# motorctrl.net
KiCad netlist of a schematic drawn in EAGLE
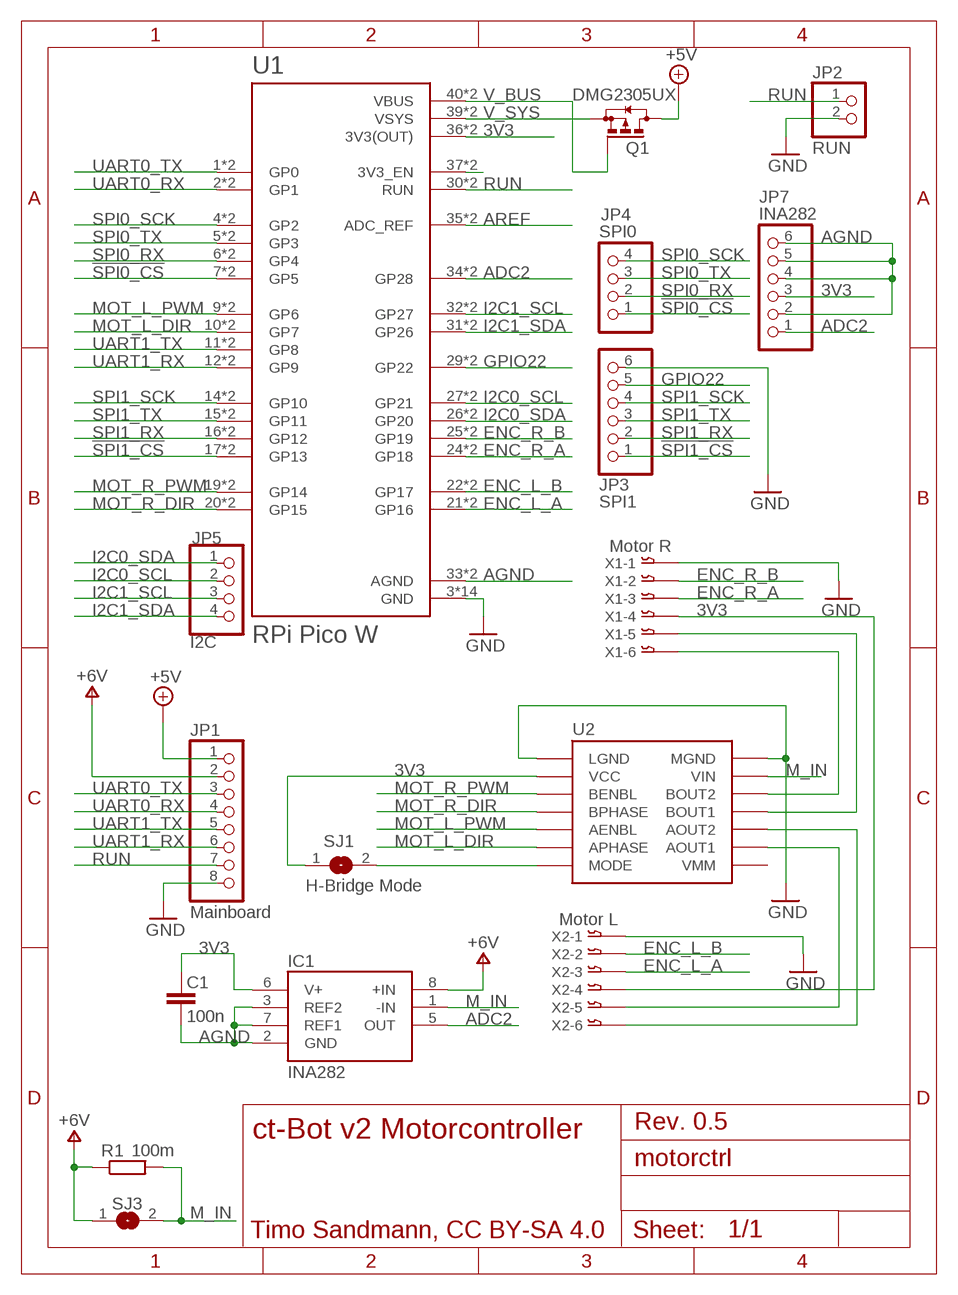
[diagram p0: schematic, sheet 1]

(export (version "E")
  (design (tool "Eeschema 10.0.6"))
  (components
    (comp (ref "C1")
      (value "100n")
      (footprint "eagle-import:C0805")
      (libsource (lib "eagle-import") (part "C-EUC0805"))
    )
    (comp (ref "IC1")
      (value "INA282")
      (footprint "eagle-import:SO08")
      (fields (field (name "MF") "TEXAS INSTRUMENTS"))
      (libsource (lib "eagle-import") (part "INA28AID"))
    )
    (comp (ref "JP1")
      (value "Mainboard")
      (footprint "eagle-import:1X08")
      (libsource (lib "eagle-import") (part "PINHD-1X8"))
    )
    (comp (ref "JP2")
      (value "RUN")
      (footprint "eagle-import:1X02")
      (libsource (lib "eagle-import") (part "PINHD-1X2"))
    )
    (comp (ref "JP3")
      (value "SPI1")
      (footprint "eagle-import:1X06")
      (libsource (lib "eagle-import") (part "PINHD-1X6"))
    )
    (comp (ref "JP4")
      (value "SPI0")
      (footprint "eagle-import:1X04")
      (libsource (lib "eagle-import") (part "PINHD-1X4"))
    )
    (comp (ref "JP5")
      (value "I2C")
      (footprint "eagle-import:1X04")
      (libsource (lib "eagle-import") (part "PINHD-1X4"))
    )
    (comp (ref "JP7")
      (value "INA282")
      (footprint "eagle-import:1X06")
      (libsource (lib "eagle-import") (part "PINHD-1X6"))
    )
    (comp (ref "Q1")
      (value "DMG2305UX")
      (footprint "eagle-import:SOT23")
      (libsource (lib "eagle-import") (part "BSS84"))
    )
    (comp (ref "R1")
      (value "100m")
      (footprint "eagle-import:R2512")
      (libsource (lib "eagle-import") (part "R-EU_R2512"))
    )
    (comp (ref "SJ1")
      (value "H-Bridge Mode")
      (footprint "eagle-import:SJ")
      (libsource (lib "eagle-import") (part "SJ"))
    )
    (comp (ref "SJ3")
      (value "VREF")
      (footprint "eagle-import:SJ")
      (libsource (lib "eagle-import") (part "SJ"))
    )
    (comp (ref "U1")
      (value "RPi Pico W")
      (footprint "eagle-import:PICO-PKG-NO_DEBUG")
      (libsource (lib "eagle-import") (part "RASPBERRY_PICO-NO_DEBUG"))
    )
    (comp (ref "U2")
      (value "DRV8835THROUGHHOLE")
      (footprint "eagle-import:DRV8835")
      (libsource (lib "eagle-import") (part "DRV8835THROUGHHOLE"))
    )
    (comp (ref "X1")
      (value "Motor R")
      (footprint "eagle-import:B6B-XH")
      (libsource (lib "eagle-import") (part "06-JST-B6B-XH-A"))
    )
    (comp (ref "X2")
      (value "Motor L")
      (footprint "eagle-import:B6B-XH")
      (libsource (lib "eagle-import") (part "06-JST-B6B-XH-A"))
    )
  )
  (nets
    (net (code "1") (name "+5V") (class "Default")
      (node (ref "JP1") (pin "1") (pinfunction "1_1") (pintype "passive"))
      (node (ref "Q1") (pin "3") (pinfunction "D_3") (pintype "passive"))
    )
    (net (code "2") (name "+6V") (class "Default")
      (node (ref "IC1") (pin "8") (pinfunction "+IN_8") (pintype "input"))
      (node (ref "JP1") (pin "2") (pinfunction "2_2") (pintype "passive"))
      (node (ref "R1") (pin "1") (pinfunction "1_1") (pintype "passive"))
      (node (ref "SJ3") (pin "1") (pinfunction "1_1") (pintype "passive"))
    )
    (net (code "3") (name "/3V3") (class "Default")
      (node (ref "C1") (pin "2") (pinfunction "2_2") (pintype "passive"))
      (node (ref "IC1") (pin "6") (pinfunction "V+_6") (pintype "power_in"))
      (node (ref "JP7") (pin "3") (pinfunction "3_3") (pintype "passive"))
      (node (ref "SJ1") (pin "1") (pinfunction "1_1") (pintype "passive"))
      (node (ref "U1") (pin "36") (pinfunction "3V3(OUT)_36") (pintype "power_in"))
      (node (ref "U1") (pin "P$36") (pinfunction "3V3(OUT)_P$36") (pintype "power_in"))
      (node (ref "U2") (pin "VCC") (pinfunction "VCC_VCC") (pintype "bidirectional"))
      (node (ref "X1") (pin "P$4") (pinfunction "1_P$4") (pintype "passive"))
      (node (ref "X2") (pin "P$4") (pinfunction "1_P$4") (pintype "passive"))
    )
    (net (code "4") (name "/ADC2") (class "Default")
      (node (ref "IC1") (pin "5") (pinfunction "OUT_5") (pintype "output"))
      (node (ref "JP7") (pin "1") (pinfunction "1_1") (pintype "passive"))
      (node (ref "U1") (pin "34") (pinfunction "GP28_34") (pintype "bidirectional"))
      (node (ref "U1") (pin "P$34") (pinfunction "GP28_P$34") (pintype "bidirectional"))
    )
    (net (code "5") (name "/AGND") (class "Default")
      (node (ref "C1") (pin "1") (pinfunction "1_1") (pintype "passive"))
      (node (ref "IC1") (pin "2") (pinfunction "GND_2") (pintype "power_in"))
      (node (ref "IC1") (pin "3") (pinfunction "REF2_3") (pintype "input"))
      (node (ref "IC1") (pin "7") (pinfunction "REF1_7") (pintype "input"))
      (node (ref "JP7") (pin "2") (pinfunction "2_2") (pintype "passive"))
      (node (ref "JP7") (pin "4") (pinfunction "4_4") (pintype "passive"))
      (node (ref "JP7") (pin "5") (pinfunction "5_5") (pintype "passive"))
      (node (ref "JP7") (pin "6") (pinfunction "6_6") (pintype "passive"))
      (node (ref "U1") (pin "33") (pinfunction "AGND_33") (pintype "input"))
      (node (ref "U1") (pin "P$33") (pinfunction "AGND_P$33") (pintype "input"))
    )
    (net (code "6") (name "/AREF") (class "Default")
      (node (ref "U1") (pin "35") (pinfunction "ADC_REF_35") (pintype "input"))
      (node (ref "U1") (pin "P$35") (pinfunction "ADC_REF_P$35") (pintype "input"))
    )
    (net (code "7") (name "/ENC_L_A") (class "Default")
      (node (ref "U1") (pin "21") (pinfunction "GP16_21") (pintype "bidirectional"))
      (node (ref "U1") (pin "P$21") (pinfunction "GP16_P$21") (pintype "bidirectional"))
      (node (ref "X2") (pin "P$3") (pinfunction "1_P$3") (pintype "passive"))
    )
    (net (code "8") (name "/ENC_L_B") (class "Default")
      (node (ref "U1") (pin "22") (pinfunction "GP17_22") (pintype "bidirectional"))
      (node (ref "U1") (pin "P$22") (pinfunction "GP17_P$22") (pintype "bidirectional"))
      (node (ref "X2") (pin "P$2") (pinfunction "1_P$2") (pintype "passive"))
    )
    (net (code "9") (name "/ENC_R_A") (class "Default")
      (node (ref "U1") (pin "24") (pinfunction "GP18_24") (pintype "bidirectional"))
      (node (ref "U1") (pin "P$24") (pinfunction "GP18_P$24") (pintype "bidirectional"))
      (node (ref "X1") (pin "P$3") (pinfunction "1_P$3") (pintype "passive"))
    )
    (net (code "10") (name "/ENC_R_B") (class "Default")
      (node (ref "U1") (pin "25") (pinfunction "GP19_25") (pintype "bidirectional"))
      (node (ref "U1") (pin "P$25") (pinfunction "GP19_P$25") (pintype "bidirectional"))
      (node (ref "X1") (pin "P$2") (pinfunction "1_P$2") (pintype "passive"))
    )
    (net (code "11") (name "/GPIO22") (class "Default")
      (node (ref "JP3") (pin "5") (pinfunction "5_5") (pintype "passive"))
      (node (ref "U1") (pin "29") (pinfunction "GP22_29") (pintype "bidirectional"))
      (node (ref "U1") (pin "P$29") (pinfunction "GP22_P$29") (pintype "bidirectional"))
    )
    (net (code "12") (name "/I2C0_SCL") (class "Default")
      (node (ref "JP5") (pin "2") (pinfunction "2_2") (pintype "passive"))
      (node (ref "U1") (pin "27") (pinfunction "GP21_27") (pintype "bidirectional"))
      (node (ref "U1") (pin "P$27") (pinfunction "GP21_P$27") (pintype "bidirectional"))
    )
    (net (code "13") (name "/I2C0_SDA") (class "Default")
      (node (ref "JP5") (pin "1") (pinfunction "1_1") (pintype "passive"))
      (node (ref "U1") (pin "26") (pinfunction "GP20_26") (pintype "bidirectional"))
      (node (ref "U1") (pin "P$26") (pinfunction "GP20_P$26") (pintype "bidirectional"))
    )
    (net (code "14") (name "/I2C1_SCL") (class "Default")
      (node (ref "JP5") (pin "3") (pinfunction "3_3") (pintype "passive"))
      (node (ref "U1") (pin "32") (pinfunction "GP27_32") (pintype "bidirectional"))
      (node (ref "U1") (pin "P$32") (pinfunction "GP27_P$32") (pintype "bidirectional"))
    )
    (net (code "15") (name "/I2C1_SDA") (class "Default")
      (node (ref "JP5") (pin "4") (pinfunction "4_4") (pintype "passive"))
      (node (ref "U1") (pin "31") (pinfunction "GP26_31") (pintype "bidirectional"))
      (node (ref "U1") (pin "P$31") (pinfunction "GP26_P$31") (pintype "bidirectional"))
    )
    (net (code "16") (name "/MOT_L_DIR") (class "Default")
      (node (ref "U1") (pin "10") (pinfunction "GP7_10") (pintype "bidirectional"))
      (node (ref "U1") (pin "P$10") (pinfunction "GP7_P$10") (pintype "bidirectional"))
      (node (ref "U2") (pin "APHASE") (pinfunction "APHASE_APHASE") (pintype "bidirectional"))
    )
    (net (code "17") (name "/MOT_L_PWM") (class "Default")
      (node (ref "U1") (pin "9") (pinfunction "GP6_9") (pintype "bidirectional"))
      (node (ref "U1") (pin "P$9") (pinfunction "GP6_P$9") (pintype "bidirectional"))
      (node (ref "U2") (pin "AENBL") (pinfunction "AENBL_AENBL") (pintype "bidirectional"))
    )
    (net (code "18") (name "/MOT_R_DIR") (class "Default")
      (node (ref "U1") (pin "20") (pinfunction "GP15_20") (pintype "bidirectional"))
      (node (ref "U1") (pin "P$20") (pinfunction "GP15_P$20") (pintype "bidirectional"))
      (node (ref "U2") (pin "BPHASE") (pinfunction "BPHASE_BPHASE") (pintype "bidirectional"))
    )
    (net (code "19") (name "/MOT_R_PWM") (class "Default")
      (node (ref "U1") (pin "19") (pinfunction "GP14_19") (pintype "bidirectional"))
      (node (ref "U1") (pin "P$19") (pinfunction "GP14_P$19") (pintype "bidirectional"))
      (node (ref "U2") (pin "BENBL") (pinfunction "BENBL_BENBL") (pintype "bidirectional"))
    )
    (net (code "20") (name "/M_IN") (class "Default")
      (node (ref "IC1") (pin "1") (pinfunction "-IN_1") (pintype "input"))
      (node (ref "R1") (pin "2") (pinfunction "2_2") (pintype "passive"))
      (node (ref "SJ3") (pin "2") (pinfunction "2_2") (pintype "passive"))
      (node (ref "U2") (pin "VIN") (pinfunction "VIN_VIN") (pintype "bidirectional"))
    )
    (net (code "21") (name "/RUN") (class "Default")
      (node (ref "JP1") (pin "7") (pinfunction "7_7") (pintype "passive"))
      (node (ref "JP2") (pin "1") (pinfunction "1_1") (pintype "passive"))
      (node (ref "U1") (pin "30") (pinfunction "RUN_30") (pintype "input"))
      (node (ref "U1") (pin "P$30") (pinfunction "RUN_P$30") (pintype "input"))
    )
    (net (code "22") (name "/SPI0_RX") (class "Default")
      (node (ref "JP4") (pin "2") (pinfunction "2_2") (pintype "passive"))
      (node (ref "U1") (pin "6") (pinfunction "GP4_6") (pintype "bidirectional"))
      (node (ref "U1") (pin "P$6") (pinfunction "GP4_P$6") (pintype "bidirectional"))
    )
    (net (code "23") (name "/SPI0_SCK") (class "Default")
      (node (ref "JP4") (pin "4") (pinfunction "4_4") (pintype "passive"))
      (node (ref "U1") (pin "4") (pinfunction "GP2_4") (pintype "bidirectional"))
      (node (ref "U1") (pin "P$4") (pinfunction "GP2_P$4") (pintype "bidirectional"))
    )
    (net (code "24") (name "/SPI0_TX") (class "Default")
      (node (ref "JP4") (pin "3") (pinfunction "3_3") (pintype "passive"))
      (node (ref "U1") (pin "5") (pinfunction "GP3_5") (pintype "bidirectional"))
      (node (ref "U1") (pin "P$5") (pinfunction "GP3_P$5") (pintype "bidirectional"))
    )
    (net (code "25") (name "/SPI1_RX") (class "Default")
      (node (ref "JP3") (pin "2") (pinfunction "2_2") (pintype "passive"))
      (node (ref "U1") (pin "16") (pinfunction "GP12_16") (pintype "bidirectional"))
      (node (ref "U1") (pin "P$16") (pinfunction "GP12_P$16") (pintype "bidirectional"))
    )
    (net (code "26") (name "/SPI1_SCK") (class "Default")
      (node (ref "JP3") (pin "4") (pinfunction "4_4") (pintype "passive"))
      (node (ref "U1") (pin "14") (pinfunction "GP10_14") (pintype "bidirectional"))
      (node (ref "U1") (pin "P$14") (pinfunction "GP10_P$14") (pintype "bidirectional"))
    )
    (net (code "27") (name "/SPI1_TX") (class "Default")
      (node (ref "JP3") (pin "3") (pinfunction "3_3") (pintype "passive"))
      (node (ref "U1") (pin "15") (pinfunction "GP11_15") (pintype "bidirectional"))
      (node (ref "U1") (pin "P$15") (pinfunction "GP11_P$15") (pintype "bidirectional"))
    )
    (net (code "28") (name "/UART0_RX") (class "Default")
      (node (ref "JP1") (pin "4") (pinfunction "4_4") (pintype "passive"))
      (node (ref "U1") (pin "2") (pinfunction "GP1_2") (pintype "bidirectional"))
      (node (ref "U1") (pin "P$2") (pinfunction "GP1_P$2") (pintype "bidirectional"))
    )
    (net (code "29") (name "/UART0_TX") (class "Default")
      (node (ref "JP1") (pin "3") (pinfunction "3_3") (pintype "passive"))
      (node (ref "U1") (pin "1") (pinfunction "GP0_1") (pintype "bidirectional"))
      (node (ref "U1") (pin "P$1") (pinfunction "GP0_P$1") (pintype "bidirectional"))
    )
    (net (code "30") (name "/UART1_RX") (class "Default")
      (node (ref "JP1") (pin "6") (pinfunction "6_6") (pintype "passive"))
      (node (ref "U1") (pin "12") (pinfunction "GP9_12") (pintype "bidirectional"))
      (node (ref "U1") (pin "P$12") (pinfunction "GP9_P$12") (pintype "bidirectional"))
    )
    (net (code "31") (name "/UART1_TX") (class "Default")
      (node (ref "JP1") (pin "5") (pinfunction "5_5") (pintype "passive"))
      (node (ref "U1") (pin "11") (pinfunction "GP8_11") (pintype "bidirectional"))
      (node (ref "U1") (pin "P$11") (pinfunction "GP8_P$11") (pintype "bidirectional"))
    )
    (net (code "32") (name "/V_BUS") (class "Default")
      (node (ref "Q1") (pin "1") (pinfunction "G_1") (pintype "passive"))
      (node (ref "U1") (pin "40") (pinfunction "VBUS_40") (pintype "power_in"))
      (node (ref "U1") (pin "P$40") (pinfunction "VBUS_P$40") (pintype "power_in"))
    )
    (net (code "33") (name "/V_SYS") (class "Default")
      (node (ref "Q1") (pin "2") (pinfunction "S_2") (pintype "passive"))
      (node (ref "U1") (pin "39") (pinfunction "VSYS_39") (pintype "power_in"))
      (node (ref "U1") (pin "P$39") (pinfunction "VSYS_P$39") (pintype "power_in"))
    )
    (net (code "34") (name "/~{SPI0_CS}") (class "Default")
      (node (ref "JP4") (pin "1") (pinfunction "1_1") (pintype "passive"))
      (node (ref "U1") (pin "7") (pinfunction "GP5_7") (pintype "bidirectional"))
      (node (ref "U1") (pin "P$7") (pinfunction "GP5_P$7") (pintype "bidirectional"))
    )
    (net (code "35") (name "/~{SPI1_CS}") (class "Default")
      (node (ref "JP3") (pin "1") (pinfunction "1_1") (pintype "passive"))
      (node (ref "U1") (pin "17") (pinfunction "GP13_17") (pintype "bidirectional"))
      (node (ref "U1") (pin "P$17") (pinfunction "GP13_P$17") (pintype "bidirectional"))
    )
    (net (code "36") (name "GND") (class "Default")
      (node (ref "JP1") (pin "8") (pinfunction "8_8") (pintype "passive"))
      (node (ref "JP2") (pin "2") (pinfunction "2_2") (pintype "passive"))
      (node (ref "JP3") (pin "6") (pinfunction "6_6") (pintype "passive"))
      (node (ref "U1") (pin "13") (pinfunction "GND_13") (pintype "power_in"))
      (node (ref "U1") (pin "18") (pinfunction "GND_18") (pintype "power_in"))
      (node (ref "U1") (pin "23") (pinfunction "GND_23") (pintype "power_in"))
      (node (ref "U1") (pin "28") (pinfunction "GND_28") (pintype "power_in"))
      (node (ref "U1") (pin "3") (pinfunction "GND_3") (pintype "power_in"))
      (node (ref "U1") (pin "38") (pinfunction "GND_38") (pintype "power_in"))
      (node (ref "U1") (pin "8") (pinfunction "GND_8") (pintype "power_in"))
      (node (ref "U1") (pin "P$13") (pinfunction "GND_P$13") (pintype "power_in"))
      (node (ref "U1") (pin "P$18") (pinfunction "GND_P$18") (pintype "power_in"))
      (node (ref "U1") (pin "P$23") (pinfunction "GND_P$23") (pintype "power_in"))
      (node (ref "U1") (pin "P$28") (pinfunction "GND_P$28") (pintype "power_in"))
      (node (ref "U1") (pin "P$3") (pinfunction "GND_P$3") (pintype "power_in"))
      (node (ref "U1") (pin "P$38") (pinfunction "GND_P$38") (pintype "power_in"))
      (node (ref "U1") (pin "P$8") (pinfunction "GND_P$8") (pintype "power_in"))
      (node (ref "U2") (pin "LGND") (pinfunction "LGND_LGND") (pintype "bidirectional"))
      (node (ref "U2") (pin "MGND") (pinfunction "MGND_MGND") (pintype "bidirectional"))
      (node (ref "X1") (pin "P$1") (pinfunction "1_P$1") (pintype "passive"))
      (node (ref "X2") (pin "P$1") (pinfunction "1_P$1") (pintype "passive"))
    )
    (net (code "37") (name "Net-(SJ1-Pad2)") (class "Default")
      (node (ref "SJ1") (pin "2") (pinfunction "2_2") (pintype "passive"))
      (node (ref "U2") (pin "MODE") (pinfunction "MODE_MODE") (pintype "bidirectional"))
    )
    (net (code "38") (name "Net-(U1-3V3_EN-Pad37)") (class "Default")
      (node (ref "U1") (pin "37") (pinfunction "3V3_EN_37") (pintype "input"))
      (node (ref "U1") (pin "P$37") (pinfunction "3V3_EN_P$37") (pintype "input"))
    )
    (net (code "39") (name "Net-(X1E-1)") (class "Default")
      (node (ref "U2") (pin "BOUT1") (pinfunction "BOUT1_BOUT1") (pintype "bidirectional"))
      (node (ref "X1") (pin "P$5") (pinfunction "1_P$5") (pintype "passive"))
    )
    (net (code "40") (name "Net-(X1F-1)") (class "Default")
      (node (ref "U2") (pin "BOUT2") (pinfunction "BOUT2_BOUT2") (pintype "bidirectional"))
      (node (ref "X1") (pin "P$6") (pinfunction "1_P$6") (pintype "passive"))
    )
    (net (code "41") (name "Net-(X2E-1)") (class "Default")
      (node (ref "U2") (pin "AOUT1") (pinfunction "AOUT1_AOUT1") (pintype "bidirectional"))
      (node (ref "X2") (pin "P$5") (pinfunction "1_P$5") (pintype "passive"))
    )
    (net (code "42") (name "Net-(X2F-1)") (class "Default")
      (node (ref "U2") (pin "AOUT2") (pinfunction "AOUT2_AOUT2") (pintype "bidirectional"))
      (node (ref "X2") (pin "P$6") (pinfunction "1_P$6") (pintype "passive"))
    )
    (net (code "43") (name "unconnected-(U2-PadVMM)") (class "Default")
      (node (ref "U2") (pin "VMM") (pinfunction "VMM_VMM") (pintype "bidirectional"))
    )
  )
)
